# Signal_Conditioning.net
KiCad netlist of a schematic drawn in Altium Designer
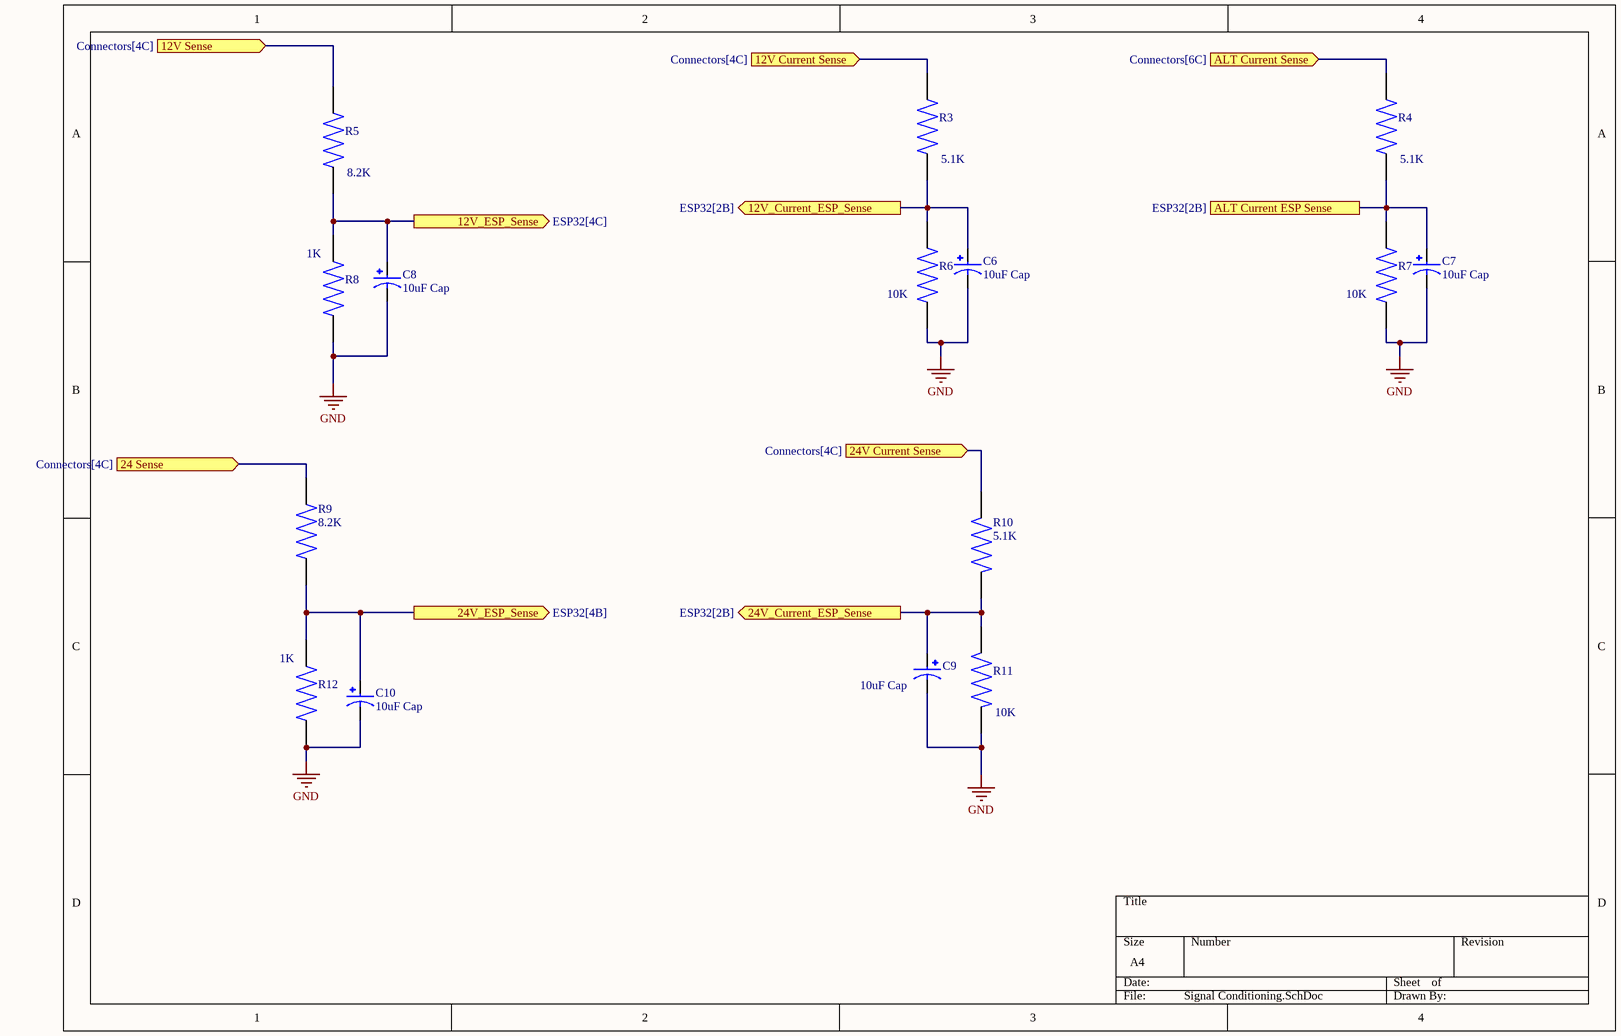
[diagram p0: Signal Conditioning.SchDoc]

(export (version "E")
  (design (tool "Eeschema 10.0.6"))
  (components
    (comp (ref "C6")
      (value "10uF Cap")
      (footprint "CAP_10uF")
      (description "CAP ALUM 10UF 20% 50V RADIAL")
      (fields (field (name "MP") "ECE-A1HN100UI") (field (name "MF") "Panasonic"))
      (libsource (lib "MySCH_Library") (part "10uF Cap"))
    )
    (comp (ref "C7")
      (value "10uF Cap")
      (footprint "CAP_10uF")
      (description "CAP ALUM 10UF 20% 50V RADIAL")
      (fields (field (name "MP") "ECE-A1HN100UI") (field (name "MF") "Panasonic"))
      (libsource (lib "MySCH_Library") (part "10uF Cap"))
    )
    (comp (ref "C8")
      (value "10uF Cap")
      (footprint "CAP_10uF")
      (description "CAP ALUM 10UF 20% 50V RADIAL")
      (fields (field (name "MP") "ECE-A1HN100UI") (field (name "MF") "Panasonic"))
      (libsource (lib "MySCH_Library") (part "10uF Cap"))
    )
    (comp (ref "C9")
      (value "10uF Cap")
      (footprint "CAP_10uF")
      (description "CAP ALUM 10UF 20% 50V RADIAL")
      (fields (field (name "MP") "ECE-A1HN100UI") (field (name "MF") "Panasonic"))
      (libsource (lib "") (part "10uF Cap_1"))
    )
    (comp (ref "C10")
      (value "10uF Cap")
      (footprint "CAP_10uF")
      (description "CAP ALUM 10UF 20% 50V RADIAL")
      (fields (field (name "MP") "ECE-A1HN100UI") (field (name "MF") "Panasonic"))
      (libsource (lib "MySCH_Library") (part "10uF Cap"))
    )
    (comp (ref "R3")
      (value "5.1K")
      (footprint "Resistor_Through Hole")
      (description "1.02 Ohms Â±1% 0.25W, 1/4W Through Hole Resistor Axial Metal Film")
      (fields (field (name "MP") "MFR-25FTE52-1R") (field (name "MF") "Yageo"))
      (libsource (lib "MySCH_Library") (part "Resistor_Through Hole"))
    )
    (comp (ref "R4")
      (value "5.1K")
      (footprint "Resistor_Through Hole")
      (description "1.02 Ohms Â±1% 0.25W, 1/4W Through Hole Resistor Axial Metal Film")
      (fields (field (name "MP") "MFR-25FTE52-1R") (field (name "MF") "Yageo"))
      (libsource (lib "MySCH_Library") (part "Resistor_Through Hole"))
    )
    (comp (ref "R5")
      (value "8.2K")
      (footprint "Resistor_Through Hole")
      (description "1.02 Ohms Â±1% 0.25W, 1/4W Through Hole Resistor Axial Metal Film")
      (fields (field (name "MP") "MFR-25FTE52-1R") (field (name "MF") "Yageo"))
      (libsource (lib "MySCH_Library") (part "Resistor_Through Hole"))
    )
    (comp (ref "R6")
      (value "10K")
      (footprint "Resistor_Through Hole")
      (description "1.02 Ohms Â±1% 0.25W, 1/4W Through Hole Resistor Axial Metal Film")
      (fields (field (name "MP") "MFR-25FTE52-1R") (field (name "MF") "Yageo"))
      (libsource (lib "MySCH_Library") (part "Resistor_Through Hole"))
    )
    (comp (ref "R7")
      (value "10K")
      (footprint "Resistor_Through Hole")
      (description "1.02 Ohms Â±1% 0.25W, 1/4W Through Hole Resistor Axial Metal Film")
      (fields (field (name "MP") "MFR-25FTE52-1R") (field (name "MF") "Yageo"))
      (libsource (lib "MySCH_Library") (part "Resistor_Through Hole"))
    )
    (comp (ref "R8")
      (value "1K")
      (footprint "Resistor_Through Hole")
      (description "1.02 Ohms Â±1% 0.25W, 1/4W Through Hole Resistor Axial Metal Film")
      (fields (field (name "MP") "MFR-25FTE52-1R") (field (name "MF") "Yageo"))
      (libsource (lib "MySCH_Library") (part "Resistor_Through Hole"))
    )
    (comp (ref "R9")
      (value "8.2K")
      (footprint "Resistor_Through Hole")
      (description "1.02 Ohms Â±1% 0.25W, 1/4W Through Hole Resistor Axial Metal Film")
      (fields (field (name "MP") "MFR-25FTE52-1R") (field (name "MF") "Yageo"))
      (libsource (lib "MySCH_Library") (part "Resistor_Through Hole"))
    )
    (comp (ref "R10")
      (value "5.1K")
      (footprint "Resistor_Through Hole")
      (description "1.02 Ohms Â±1% 0.25W, 1/4W Through Hole Resistor Axial Metal Film")
      (fields (field (name "MP") "MFR-25FTE52-1R") (field (name "MF") "Yageo"))
      (libsource (lib "MySCH_Library") (part "Resistor_Through Hole"))
    )
    (comp (ref "R11")
      (value "10K")
      (footprint "Resistor_Through Hole")
      (description "1.02 Ohms Â±1% 0.25W, 1/4W Through Hole Resistor Axial Metal Film")
      (fields (field (name "MP") "MFR-25FTE52-1R") (field (name "MF") "Yageo"))
      (libsource (lib "MySCH_Library") (part "Resistor_Through Hole"))
    )
    (comp (ref "R12")
      (value "1K")
      (footprint "Resistor_Through Hole")
      (description "1.02 Ohms Â±1% 0.25W, 1/4W Through Hole Resistor Axial Metal Film")
      (fields (field (name "MP") "MFR-25FTE52-1R") (field (name "MF") "Yageo"))
      (libsource (lib "MySCH_Library") (part "Resistor_Through Hole"))
    )
  )
  (nets
    (net (code "1") (name "/12V Current Sense") (class "Default")
      (node (ref "R3") (pin "2") (pinfunction "2_2") (pintype "passive"))
    )
    (net (code "2") (name "/12V Sense") (class "Default")
      (node (ref "R5") (pin "2") (pinfunction "2_2") (pintype "passive"))
    )
    (net (code "3") (name "/12V_Current_ESP_Sense") (class "Default")
      (node (ref "C6") (pin "P") (pinfunction "P_P") (pintype "passive"))
      (node (ref "R3") (pin "1") (pinfunction "1_1") (pintype "passive"))
      (node (ref "R6") (pin "2") (pinfunction "2_2") (pintype "passive"))
    )
    (net (code "4") (name "/12V_ESP_Sense") (class "Default")
      (node (ref "C8") (pin "P") (pinfunction "P_P") (pintype "passive"))
      (node (ref "R5") (pin "1") (pinfunction "1_1") (pintype "passive"))
      (node (ref "R8") (pin "2") (pinfunction "2_2") (pintype "passive"))
    )
    (net (code "5") (name "/24 Sense") (class "Default")
      (node (ref "R9") (pin "1") (pinfunction "1_1") (pintype "passive"))
    )
    (net (code "6") (name "/24V Current Sense") (class "Default")
      (node (ref "R10") (pin "2") (pinfunction "2_2") (pintype "passive"))
    )
    (net (code "7") (name "/24V_Current_ESP_Sense") (class "Default")
      (node (ref "C9") (pin "P") (pinfunction "P_P") (pintype "passive"))
      (node (ref "R10") (pin "1") (pinfunction "1_1") (pintype "passive"))
      (node (ref "R11") (pin "2") (pinfunction "2_2") (pintype "passive"))
    )
    (net (code "8") (name "/24V_ESP_Sense") (class "Default")
      (node (ref "C10") (pin "P") (pinfunction "P_P") (pintype "passive"))
      (node (ref "R12") (pin "2") (pinfunction "2_2") (pintype "passive"))
      (node (ref "R9") (pin "2") (pinfunction "2_2") (pintype "passive"))
    )
    (net (code "9") (name "/ALT Current ESP Sense") (class "Default")
      (node (ref "C7") (pin "P") (pinfunction "P_P") (pintype "passive"))
      (node (ref "R4") (pin "1") (pinfunction "1_1") (pintype "passive"))
      (node (ref "R7") (pin "2") (pinfunction "2_2") (pintype "passive"))
    )
    (net (code "10") (name "/ALT Current Sense") (class "Default")
      (node (ref "R4") (pin "2") (pinfunction "2_2") (pintype "passive"))
    )
    (net (code "11") (name "GND") (class "Default")
      (node (ref "C10") (pin "N") (pinfunction "N_N") (pintype "passive"))
      (node (ref "C6") (pin "N") (pinfunction "N_N") (pintype "passive"))
      (node (ref "C7") (pin "N") (pinfunction "N_N") (pintype "passive"))
      (node (ref "C8") (pin "N") (pinfunction "N_N") (pintype "passive"))
      (node (ref "C9") (pin "N") (pinfunction "N_N") (pintype "passive"))
      (node (ref "R11") (pin "1") (pinfunction "1_1") (pintype "passive"))
      (node (ref "R12") (pin "1") (pinfunction "1_1") (pintype "passive"))
      (node (ref "R6") (pin "1") (pinfunction "1_1") (pintype "passive"))
      (node (ref "R7") (pin "1") (pinfunction "1_1") (pintype "passive"))
      (node (ref "R8") (pin "1") (pinfunction "1_1") (pintype "passive"))
    )
  )
)
